# Clock_fab.net
KiCad netlist of a schematic drawn in EAGLE
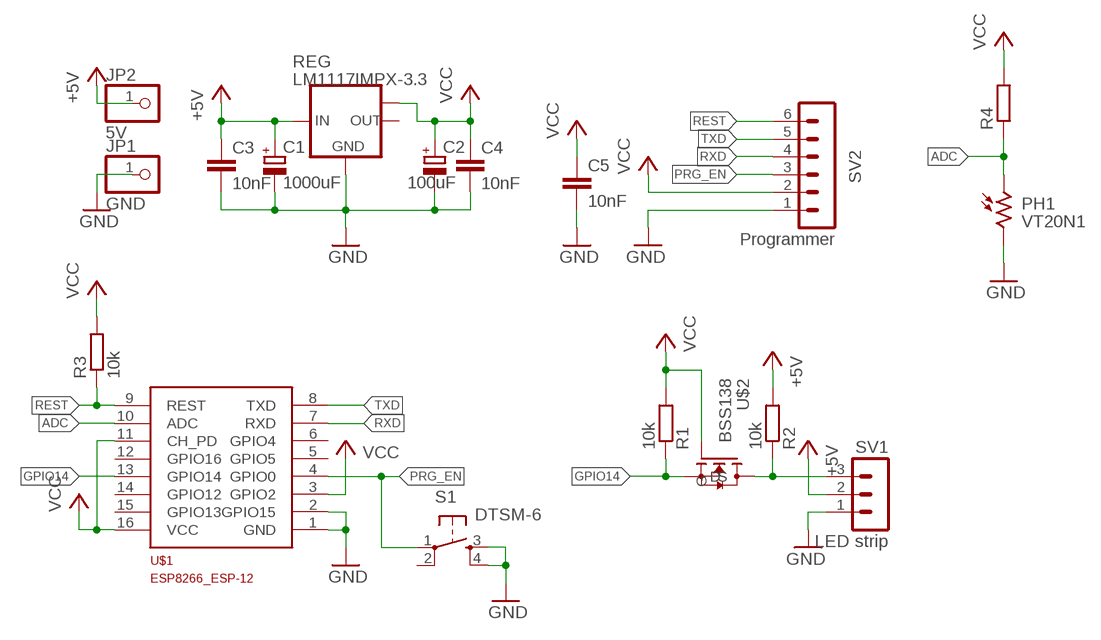
[diagram p0: schematic, sheet 1]

(export (version "E")
  (design (tool "Eeschema 10.0.6"))
  (components
    (comp (ref "C1")
      (value "1000uF")
      (footprint "eagle-import:TT5D11L")
      (libsource (lib "eagle-import") (part "CPOL-EUTT5D11L"))
    )
    (comp (ref "C2")
      (value "100uF")
      (footprint "eagle-import:TT5D7L")
      (libsource (lib "eagle-import") (part "CPOL-EUTT5D7L"))
    )
    (comp (ref "C3")
      (value "10nF")
      (footprint "eagle-import:C0805")
      (libsource (lib "eagle-import") (part "C-EUC0805"))
    )
    (comp (ref "C4")
      (value "10nF")
      (footprint "eagle-import:C0805")
      (libsource (lib "eagle-import") (part "C-EUC0805"))
    )
    (comp (ref "C5")
      (value "10nF")
      (footprint "eagle-import:C0805")
      (libsource (lib "eagle-import") (part "C-EUC0805"))
    )
    (comp (ref "JP1")
      (value "GND")
      (footprint "eagle-import:1X01")
      (libsource (lib "eagle-import") (part "PINHD-1X1"))
    )
    (comp (ref "JP2")
      (value "5V")
      (footprint "eagle-import:1X01")
      (libsource (lib "eagle-import") (part "PINHD-1X1"))
    )
    (comp (ref "PH1")
      (value "VT20N1")
      (footprint "eagle-import:TO46-VT200")
      (libsource (lib "eagle-import") (part "VT20N1"))
    )
    (comp (ref "R1")
      (value "10k")
      (footprint "eagle-import:R0805")
      (libsource (lib "eagle-import") (part "R-EU_R0805"))
    )
    (comp (ref "R2")
      (value "10k")
      (footprint "eagle-import:R0805")
      (libsource (lib "eagle-import") (part "R-EU_R0805"))
    )
    (comp (ref "R3")
      (value "10k")
      (footprint "eagle-import:R0805")
      (libsource (lib "eagle-import") (part "R-EU_R0805"))
    )
    (comp (ref "R4")
      (value "R-EU_R0805")
      (footprint "eagle-import:R0805")
      (libsource (lib "eagle-import") (part "R-EU_R0805"))
    )
    (comp (ref "REG")
      (value "LM1117IMPX-3.3")
      (footprint "eagle-import:SOT223")
      (libsource (lib "eagle-import") (part "LM1117IMPX-3.3"))
    )
    (comp (ref "S1")
      (value "DTSM-6")
      (footprint "eagle-import:DTSM-6")
      (libsource (lib "eagle-import") (part "DTSM-6"))
    )
    (comp (ref "SV1")
      (value "LED strip")
      (footprint "eagle-import:MA03-1")
      (libsource (lib "eagle-import") (part "MA03-1"))
    )
    (comp (ref "SV2")
      (value "Programmer")
      (footprint "eagle-import:MA06-1")
      (libsource (lib "eagle-import") (part "MA06-1"))
    )
    (comp (ref "U$1")
      (value "ESP8266_ESP-12")
      (footprint "eagle-import:ESP8266-ESP12")
      (libsource (lib "eagle-import") (part "ESP8266_ESP-12"))
    )
    (comp (ref "U$2")
      (value "BSS138")
      (footprint "eagle-import:BSS138")
      (fields (field (name "MF") "Fairchild Semiconductor"))
      (libsource (lib "eagle-import") (part "BSS138"))
    )
  )
  (nets
    (net (code "1") (name "+5V") (class "Default")
      (node (ref "C1") (pin "+") (pinfunction "+_+") (pintype "passive"))
      (node (ref "C3") (pin "1") (pinfunction "1_1") (pintype "passive"))
      (node (ref "JP2") (pin "1") (pinfunction "1_1") (pintype "passive"))
      (node (ref "R2") (pin "2") (pinfunction "2_2") (pintype "passive"))
      (node (ref "REG") (pin "3") (pinfunction "IN_3") (pintype "input"))
      (node (ref "SV1") (pin "2") (pinfunction "2_2") (pintype "passive"))
    )
    (net (code "2") (name "ADC") (class "Default")
      (node (ref "PH1") (pin "1") (pinfunction "1_1") (pintype "passive"))
      (node (ref "R4") (pin "1") (pinfunction "1_1") (pintype "passive"))
      (node (ref "U$1") (pin "10") (pinfunction "ADC_10") (pintype "bidirectional"))
    )
    (net (code "3") (name "GND") (class "Default")
      (node (ref "C1") (pin "-") (pinfunction "-_-") (pintype "passive"))
      (node (ref "C2") (pin "-") (pinfunction "-_-") (pintype "passive"))
      (node (ref "C3") (pin "2") (pinfunction "2_2") (pintype "passive"))
      (node (ref "C4") (pin "2") (pinfunction "2_2") (pintype "passive"))
      (node (ref "C5") (pin "2") (pinfunction "2_2") (pintype "passive"))
      (node (ref "JP1") (pin "1") (pinfunction "1_1") (pintype "passive"))
      (node (ref "PH1") (pin "2") (pinfunction "2_2") (pintype "passive"))
      (node (ref "REG") (pin "1") (pinfunction "GND_1") (pintype "input"))
      (node (ref "S1") (pin "3") (pinfunction "3_3") (pintype "passive"))
      (node (ref "S1") (pin "4") (pinfunction "4_4") (pintype "passive"))
      (node (ref "SV1") (pin "1") (pinfunction "1_1") (pintype "passive"))
      (node (ref "SV2") (pin "1") (pinfunction "1_1") (pintype "passive"))
      (node (ref "U$1") (pin "1") (pinfunction "GND_1") (pintype "bidirectional"))
      (node (ref "U$1") (pin "2") (pinfunction "GPIO15_2") (pintype "bidirectional"))
    )
    (net (code "4") (name "GPIO14") (class "Default")
      (node (ref "R1") (pin "1") (pinfunction "1_1") (pintype "passive"))
      (node (ref "U$1") (pin "13") (pinfunction "GPIO14_13") (pintype "bidirectional"))
      (node (ref "U$2") (pin "S") (pinfunction "S_S") (pintype "passive"))
    )
    (net (code "5") (name "Net-(R2-Pad1)") (class "Default")
      (node (ref "R2") (pin "1") (pinfunction "1_1") (pintype "passive"))
      (node (ref "SV1") (pin "3") (pinfunction "3_3") (pintype "passive"))
      (node (ref "U$2") (pin "D") (pinfunction "D_D") (pintype "passive"))
    )
    (net (code "6") (name "PRG_EN") (class "Default")
      (node (ref "S1") (pin "1") (pinfunction "1_1") (pintype "passive"))
      (node (ref "SV2") (pin "3") (pinfunction "3_3") (pintype "passive"))
      (node (ref "U$1") (pin "4") (pinfunction "GPIO0_4") (pintype "bidirectional"))
    )
    (net (code "7") (name "REST") (class "Default")
      (node (ref "R3") (pin "1") (pinfunction "1_1") (pintype "passive"))
      (node (ref "SV2") (pin "6") (pinfunction "6_6") (pintype "passive"))
      (node (ref "U$1") (pin "9") (pinfunction "REST_9") (pintype "bidirectional"))
    )
    (net (code "8") (name "RXD") (class "Default")
      (node (ref "SV2") (pin "4") (pinfunction "4_4") (pintype "passive"))
      (node (ref "U$1") (pin "7") (pinfunction "RXD_7") (pintype "bidirectional"))
    )
    (net (code "9") (name "TXD") (class "Default")
      (node (ref "SV2") (pin "5") (pinfunction "5_5") (pintype "passive"))
      (node (ref "U$1") (pin "8") (pinfunction "TXD_8") (pintype "bidirectional"))
    )
    (net (code "10") (name "VCC") (class "Default")
      (node (ref "C2") (pin "+") (pinfunction "+_+") (pintype "passive"))
      (node (ref "C4") (pin "1") (pinfunction "1_1") (pintype "passive"))
      (node (ref "C5") (pin "1") (pinfunction "1_1") (pintype "passive"))
      (node (ref "R1") (pin "2") (pinfunction "2_2") (pintype "passive"))
      (node (ref "R3") (pin "2") (pinfunction "2_2") (pintype "passive"))
      (node (ref "R4") (pin "2") (pinfunction "2_2") (pintype "passive"))
      (node (ref "REG") (pin "TAB") (pinfunction "OUT1_TAB") (pintype "passive"))
      (node (ref "SV2") (pin "2") (pinfunction "2_2") (pintype "passive"))
      (node (ref "U$1") (pin "11") (pinfunction "CH_PD_11") (pintype "bidirectional"))
      (node (ref "U$1") (pin "16") (pinfunction "VCC_16") (pintype "bidirectional"))
      (node (ref "U$1") (pin "3") (pinfunction "GPIO2_3") (pintype "bidirectional"))
      (node (ref "U$2") (pin "G") (pinfunction "G_G") (pintype "passive"))
    )
    (net (code "11") (name "unconnected-(REG-OUT-Pad2)") (class "Default")
      (node (ref "REG") (pin "2") (pinfunction "OUT_2") (pintype "passive"))
    )
    (net (code "12") (name "unconnected-(S1-Pad2)") (class "Default")
      (node (ref "S1") (pin "2") (pinfunction "2_2") (pintype "passive"))
    )
    (net (code "13") (name "unconnected-(U$1-GPIO4-Pad6)") (class "Default")
      (node (ref "U$1") (pin "6") (pinfunction "GPIO4_6") (pintype "bidirectional"))
    )
    (net (code "14") (name "unconnected-(U$1-GPIO5-Pad5)") (class "Default")
      (node (ref "U$1") (pin "5") (pinfunction "GPIO5_5") (pintype "bidirectional"))
    )
    (net (code "15") (name "unconnected-(U$1-GPIO12-Pad14)") (class "Default")
      (node (ref "U$1") (pin "14") (pinfunction "GPIO12_14") (pintype "bidirectional"))
    )
    (net (code "16") (name "unconnected-(U$1-GPIO13-Pad15)") (class "Default")
      (node (ref "U$1") (pin "15") (pinfunction "GPIO13_15") (pintype "bidirectional"))
    )
    (net (code "17") (name "unconnected-(U$1-GPIO16-Pad12)") (class "Default")
      (node (ref "U$1") (pin "12") (pinfunction "GPIO16_12") (pintype "bidirectional"))
    )
  )
)
